# Driver.net
KiCad netlist of a schematic drawn in EAGLE
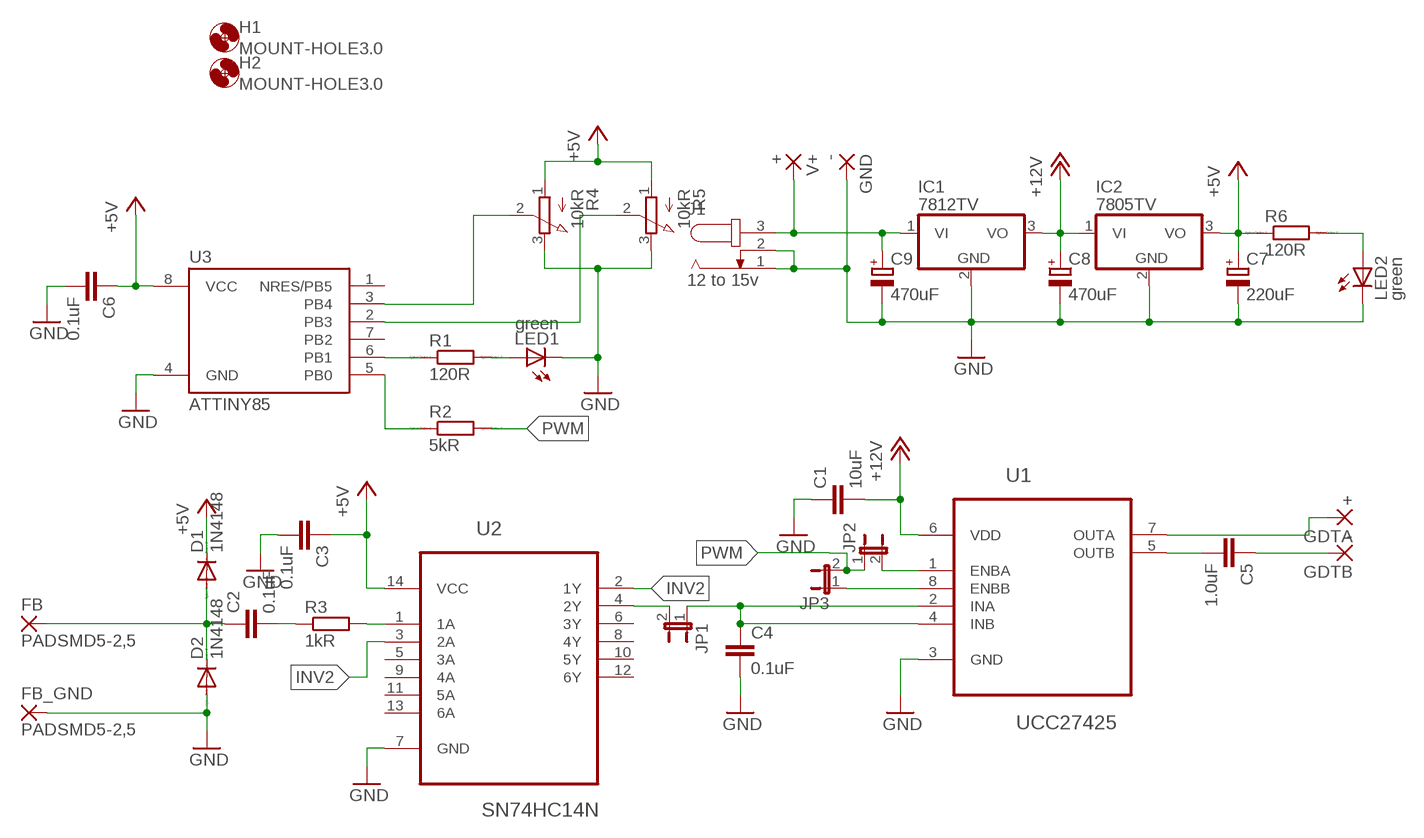
[diagram p0: schematic, sheet 1]

(export (version "E")
  (design (tool "Eeschema 10.0.6"))
  (components
    (comp (ref "C1")
      (value "10uF")
      (footprint "eagle-import:1210")
      (libsource (lib "eagle-import") (part "10UF-1210-50V-20%"))
    )
    (comp (ref "C2")
      (value "0.1uF")
      (footprint "eagle-import:C0805")
      (libsource (lib "eagle-import") (part "C-EUC0805"))
    )
    (comp (ref "C3")
      (value "0.1uF")
      (footprint "eagle-import:C0805")
      (libsource (lib "eagle-import") (part "C-EUC0805"))
    )
    (comp (ref "C4")
      (value "0.1uF")
      (footprint "eagle-import:C0805")
      (libsource (lib "eagle-import") (part "C-EUC0805"))
    )
    (comp (ref "C5")
      (value "1.0uF")
      (footprint "eagle-import:0805")
      (libsource (lib "eagle-import") (part "1.0UF-0805-25V-10%"))
    )
    (comp (ref "C6")
      (value "0.1uF")
      (footprint "eagle-import:C0805")
      (libsource (lib "eagle-import") (part "C-EUC0805"))
    )
    (comp (ref "C7")
      (value "220uF")
      (footprint "eagle-import:E3,5-8")
      (libsource (lib "eagle-import") (part "CPOL-EUE3.5-8"))
    )
    (comp (ref "C8")
      (value "470uF")
      (footprint "eagle-import:E3,5-10")
      (libsource (lib "eagle-import") (part "CPOL-EUE3.5-10"))
    )
    (comp (ref "C9")
      (value "470uF")
      (footprint "eagle-import:E3,5-10")
      (libsource (lib "eagle-import") (part "CPOL-EUE3.5-10"))
    )
    (comp (ref "D1")
      (value "1N4148")
      (footprint "eagle-import:DO35-7")
      (libsource (lib "eagle-import") (part "1N4148DO35-7"))
    )
    (comp (ref "D2")
      (value "1N4148")
      (footprint "eagle-import:DO35-7")
      (libsource (lib "eagle-import") (part "1N4148DO35-7"))
    )
    (comp (ref "FB")
      (value "PADSMD5-2,5")
      (footprint "eagle-import:5-2,5")
      (libsource (lib "eagle-import") (part "WIREPADSMD5-2,5"))
    )
    (comp (ref "FB_GND")
      (value "PADSMD5-2,5")
      (footprint "eagle-import:5-2,5")
      (libsource (lib "eagle-import") (part "WIREPADSMD5-2,5"))
    )
    (comp (ref "GDTA")
      (value "+")
      (footprint "eagle-import:4,16O1,6")
      (libsource (lib "eagle-import") (part "WIREPAD4,16O1,6"))
    )
    (comp (ref "GDTB")
      (value "-")
      (footprint "eagle-import:4,16O1,6")
      (libsource (lib "eagle-import") (part "WIREPAD4,16O1,6"))
    )
    (comp (ref "GND")
      (value "-")
      (footprint "eagle-import:4,16O1,6")
      (libsource (lib "eagle-import") (part "WIREPAD4,16O1,6"))
    )
    (comp (ref "H1")
      (value "MOUNT-HOLE3.0")
      (footprint "eagle-import:3,0")
      (libsource (lib "eagle-import") (part "MOUNT-HOLE3.0"))
    )
    (comp (ref "H2")
      (value "MOUNT-HOLE3.0")
      (footprint "eagle-import:3,0")
      (libsource (lib "eagle-import") (part "MOUNT-HOLE3.0"))
    )
    (comp (ref "IC1")
      (value "7812TV")
      (footprint "eagle-import:TO220V")
      (libsource (lib "eagle-import") (part "78TV12"))
    )
    (comp (ref "IC2")
      (value "7805TV")
      (footprint "eagle-import:TO220V")
      (libsource (lib "eagle-import") (part "78TV05"))
    )
    (comp (ref "J1")
      (value "12 to 15v")
      (footprint "eagle-import:SPC4078")
      (libsource (lib "eagle-import") (part "JACK-PLUG1"))
    )
    (comp (ref "JP1")
      (value "JP1E")
      (footprint "eagle-import:JP1")
      (libsource (lib "eagle-import") (part "JP1E"))
    )
    (comp (ref "JP2")
      (value "JP1E")
      (footprint "eagle-import:JP1")
      (libsource (lib "eagle-import") (part "JP1E"))
    )
    (comp (ref "JP3")
      (value "JP1E")
      (footprint "eagle-import:JP1")
      (libsource (lib "eagle-import") (part "JP1E"))
    )
    (comp (ref "LED1")
      (value "green")
      (footprint "eagle-import:CHIPLED_0805")
      (libsource (lib "eagle-import") (part "LEDCHIPLED_0805"))
    )
    (comp (ref "LED2")
      (value "green")
      (footprint "eagle-import:CHIPLED_0805")
      (libsource (lib "eagle-import") (part "LEDCHIPLED_0805"))
    )
    (comp (ref "R1")
      (value "120R")
      (footprint "eagle-import:R0805")
      (libsource (lib "eagle-import") (part "R"))
    )
    (comp (ref "R2")
      (value "5kR")
      (footprint "eagle-import:R0805")
      (libsource (lib "eagle-import") (part "R"))
    )
    (comp (ref "R3")
      (value "1kR")
      (footprint "eagle-import:R0805")
      (libsource (lib "eagle-import") (part "R-EU_R0805"))
    )
    (comp (ref "R4")
      (value "10kR")
      (footprint "eagle-import:3RP_1610N")
      (libsource (lib "eagle-import") (part "3RP/1610N"))
    )
    (comp (ref "R5")
      (value "10kR")
      (footprint "eagle-import:3RP_1610N")
      (libsource (lib "eagle-import") (part "3RP/1610N"))
    )
    (comp (ref "R6")
      (value "120R")
      (footprint "eagle-import:R0805")
      (libsource (lib "eagle-import") (part "R"))
    )
    (comp (ref "U1")
      (value "UCC27425")
      (footprint "eagle-import:DIP254P762X419-8")
      (libsource (lib "eagle-import") (part "UCC27425QDRQ1DIP_8"))
    )
    (comp (ref "U2")
      (value "SN74HC14N")
      (footprint "eagle-import:DIP254P762X508-14")
      (libsource (lib "eagle-import") (part "SN74HC14N"))
    )
    (comp (ref "U3")
      (value "ATTINY85")
      (footprint "eagle-import:DIL08")
      (libsource (lib "eagle-import") (part "ATTINY85DIL"))
    )
    (comp (ref "V+")
      (value "+")
      (footprint "eagle-import:4,16O1,6")
      (libsource (lib "eagle-import") (part "WIREPAD4,16O1,6"))
    )
  )
  (nets
    (net (code "1") (name "+5V") (class "Default")
      (node (ref "C3") (pin "1") (pinfunction "1_1") (pintype "passive"))
      (node (ref "C6") (pin "1") (pinfunction "1_1") (pintype "passive"))
      (node (ref "C7") (pin "+") (pinfunction "+_+") (pintype "passive"))
      (node (ref "D1") (pin "C") (pinfunction "C_C") (pintype "passive"))
      (node (ref "IC2") (pin "3") (pinfunction "VO_3") (pintype "passive"))
      (node (ref "R4") (pin "1") (pinfunction "A_1") (pintype "passive"))
      (node (ref "R5") (pin "1") (pinfunction "A_1") (pintype "passive"))
      (node (ref "R6") (pin "1") (pinfunction "1_1") (pintype "passive"))
      (node (ref "U2") (pin "14") (pinfunction "VCC_14") (pintype "power_in"))
      (node (ref "U3") (pin "8") (pinfunction "VCC_8") (pintype "power_in"))
    )
    (net (code "2") (name "+12V") (class "Default")
      (node (ref "C1") (pin "2") (pinfunction "2_2") (pintype "passive"))
      (node (ref "C8") (pin "+") (pinfunction "+_+") (pintype "passive"))
      (node (ref "IC1") (pin "3") (pinfunction "VO_3") (pintype "passive"))
      (node (ref "IC2") (pin "1") (pinfunction "VI_1") (pintype "input"))
      (node (ref "U1") (pin "6") (pinfunction "VDD_6") (pintype "power_in"))
    )
    (net (code "3") (name "GND") (class "Default")
      (node (ref "C1") (pin "1") (pinfunction "1_1") (pintype "passive"))
      (node (ref "C3") (pin "2") (pinfunction "2_2") (pintype "passive"))
      (node (ref "C4") (pin "2") (pinfunction "2_2") (pintype "passive"))
      (node (ref "C6") (pin "2") (pinfunction "2_2") (pintype "passive"))
      (node (ref "C7") (pin "-") (pinfunction "-_-") (pintype "passive"))
      (node (ref "C8") (pin "-") (pinfunction "-_-") (pintype "passive"))
      (node (ref "C9") (pin "-") (pinfunction "-_-") (pintype "passive"))
      (node (ref "D2") (pin "A") (pinfunction "A_A") (pintype "passive"))
      (node (ref "FB_GND") (pin "1") (pinfunction "P_1") (pintype "passive"))
      (node (ref "GND") (pin "1") (pinfunction "P_1") (pintype "passive"))
      (node (ref "IC1") (pin "2") (pinfunction "GND_2") (pintype "passive"))
      (node (ref "IC2") (pin "2") (pinfunction "GND_2") (pintype "passive"))
      (node (ref "J1") (pin "1") (pinfunction "1_1") (pintype "passive"))
      (node (ref "J1") (pin "2") (pinfunction "2_2") (pintype "passive"))
      (node (ref "LED1") (pin "C") (pinfunction "C_C") (pintype "passive"))
      (node (ref "LED2") (pin "C") (pinfunction "C_C") (pintype "passive"))
      (node (ref "R4") (pin "3") (pinfunction "E_3") (pintype "passive"))
      (node (ref "R5") (pin "3") (pinfunction "E_3") (pintype "passive"))
      (node (ref "U1") (pin "3") (pinfunction "GND_3") (pintype "passive"))
      (node (ref "U2") (pin "7") (pinfunction "GND_7") (pintype "passive"))
      (node (ref "U3") (pin "4") (pinfunction "GND_4") (pintype "power_in"))
    )
    (net (code "4") (name "INV2") (class "Default")
      (node (ref "U2") (pin "2") (pinfunction "1Y_2") (pintype "output"))
      (node (ref "U2") (pin "3") (pinfunction "2A_3") (pintype "input"))
    )
    (net (code "5") (name "Net-(C2-Pad2)") (class "Default")
      (node (ref "C2") (pin "2") (pinfunction "2_2") (pintype "passive"))
      (node (ref "R3") (pin "1") (pinfunction "1_1") (pintype "passive"))
    )
    (net (code "6") (name "Net-(FB-P)") (class "Default")
      (node (ref "C2") (pin "1") (pinfunction "1_1") (pintype "passive"))
      (node (ref "D1") (pin "A") (pinfunction "A_A") (pintype "passive"))
      (node (ref "D2") (pin "C") (pinfunction "C_C") (pintype "passive"))
      (node (ref "FB") (pin "1") (pinfunction "P_1") (pintype "passive"))
    )
    (net (code "7") (name "Net-(GDTA-P)") (class "Default")
      (node (ref "GDTA") (pin "1") (pinfunction "P_1") (pintype "passive"))
      (node (ref "U1") (pin "7") (pinfunction "OUTA_7") (pintype "output"))
    )
    (net (code "8") (name "Net-(GDTB-P)") (class "Default")
      (node (ref "C5") (pin "1") (pinfunction "1_1") (pintype "passive"))
      (node (ref "GDTB") (pin "1") (pinfunction "P_1") (pintype "passive"))
    )
    (net (code "9") (name "Net-(IC1-VI)") (class "Default")
      (node (ref "C9") (pin "+") (pinfunction "+_+") (pintype "passive"))
      (node (ref "IC1") (pin "1") (pinfunction "VI_1") (pintype "input"))
      (node (ref "J1") (pin "3") (pinfunction "3_3") (pintype "passive"))
      (node (ref "V+") (pin "1") (pinfunction "P_1") (pintype "passive"))
    )
    (net (code "10") (name "Net-(LED1-PadA)") (class "Default")
      (node (ref "LED1") (pin "A") (pinfunction "A_A") (pintype "passive"))
      (node (ref "R1") (pin "2") (pinfunction "2_2") (pintype "passive"))
    )
    (net (code "11") (name "Net-(LED2-PadA)") (class "Default")
      (node (ref "LED2") (pin "A") (pinfunction "A_A") (pintype "passive"))
      (node (ref "R6") (pin "2") (pinfunction "2_2") (pintype "passive"))
    )
    (net (code "12") (name "Net-(R4-S)") (class "Default")
      (node (ref "R4") (pin "2") (pinfunction "S_2") (pintype "passive"))
      (node (ref "U3") (pin "3") (pinfunction "PB4_3") (pintype "bidirectional"))
    )
    (net (code "13") (name "Net-(R5-S)") (class "Default")
      (node (ref "R5") (pin "2") (pinfunction "S_2") (pintype "passive"))
      (node (ref "U3") (pin "2") (pinfunction "PB3_2") (pintype "bidirectional"))
    )
    (net (code "14") (name "Net-(U1-ENBA)") (class "Default")
      (node (ref "JP2") (pin "2") (pinfunction "2_2") (pintype "passive"))
      (node (ref "U1") (pin "1") (pinfunction "ENBA_1") (pintype "input"))
    )
    (net (code "15") (name "Net-(U1-ENBB)") (class "Default")
      (node (ref "JP3") (pin "1") (pinfunction "1_1") (pintype "passive"))
      (node (ref "U1") (pin "8") (pinfunction "ENBB_8") (pintype "input"))
    )
    (net (code "16") (name "Net-(U1-INA)") (class "Default")
      (node (ref "C4") (pin "1") (pinfunction "1_1") (pintype "passive"))
      (node (ref "JP1") (pin "1") (pinfunction "1_1") (pintype "passive"))
      (node (ref "U1") (pin "2") (pinfunction "INA_2") (pintype "input"))
      (node (ref "U1") (pin "4") (pinfunction "INB_4") (pintype "input"))
    )
    (net (code "17") (name "Net-(U1-OUTB)") (class "Default")
      (node (ref "C5") (pin "2") (pinfunction "2_2") (pintype "passive"))
      (node (ref "U1") (pin "5") (pinfunction "OUTB_5") (pintype "output"))
    )
    (net (code "18") (name "Net-(U2-1A)") (class "Default")
      (node (ref "R3") (pin "2") (pinfunction "2_2") (pintype "passive"))
      (node (ref "U2") (pin "1") (pinfunction "1A_1") (pintype "input"))
    )
    (net (code "19") (name "Net-(U2-2Y)") (class "Default")
      (node (ref "JP1") (pin "2") (pinfunction "2_2") (pintype "passive"))
      (node (ref "U2") (pin "4") (pinfunction "2Y_4") (pintype "output"))
    )
    (net (code "20") (name "Net-(U3-PB0)") (class "Default")
      (node (ref "R2") (pin "1") (pinfunction "1_1") (pintype "passive"))
      (node (ref "U3") (pin "5") (pinfunction "PB0_5") (pintype "bidirectional"))
    )
    (net (code "21") (name "Net-(U3-PB1)") (class "Default")
      (node (ref "R1") (pin "1") (pinfunction "1_1") (pintype "passive"))
      (node (ref "U3") (pin "6") (pinfunction "PB1_6") (pintype "bidirectional"))
    )
    (net (code "22") (name "PWM") (class "Default")
      (node (ref "JP2") (pin "1") (pinfunction "1_1") (pintype "passive"))
      (node (ref "JP3") (pin "2") (pinfunction "2_2") (pintype "passive"))
      (node (ref "R2") (pin "2") (pinfunction "2_2") (pintype "passive"))
    )
    (net (code "23") (name "unconnected-(U2-3A-Pad5)") (class "Default")
      (node (ref "U2") (pin "5") (pinfunction "3A_5") (pintype "input"))
    )
    (net (code "24") (name "unconnected-(U2-3Y-Pad6)") (class "Default")
      (node (ref "U2") (pin "6") (pinfunction "3Y_6") (pintype "output"))
    )
    (net (code "25") (name "unconnected-(U2-4A-Pad9)") (class "Default")
      (node (ref "U2") (pin "9") (pinfunction "4A_9") (pintype "input"))
    )
    (net (code "26") (name "unconnected-(U2-4Y-Pad8)") (class "Default")
      (node (ref "U2") (pin "8") (pinfunction "4Y_8") (pintype "output"))
    )
    (net (code "27") (name "unconnected-(U2-5A-Pad11)") (class "Default")
      (node (ref "U2") (pin "11") (pinfunction "5A_11") (pintype "input"))
    )
    (net (code "28") (name "unconnected-(U2-5Y-Pad10)") (class "Default")
      (node (ref "U2") (pin "10") (pinfunction "5Y_10") (pintype "output"))
    )
    (net (code "29") (name "unconnected-(U2-6A-Pad13)") (class "Default")
      (node (ref "U2") (pin "13") (pinfunction "6A_13") (pintype "input"))
    )
    (net (code "30") (name "unconnected-(U2-6Y-Pad12)") (class "Default")
      (node (ref "U2") (pin "12") (pinfunction "6Y_12") (pintype "output"))
    )
    (net (code "31") (name "unconnected-(U3-NRES{slash}PB5-Pad1)") (class "Default")
      (node (ref "U3") (pin "1") (pinfunction "NRES/PB5_1") (pintype "bidirectional"))
    )
    (net (code "32") (name "unconnected-(U3-PB2-Pad7)") (class "Default")
      (node (ref "U3") (pin "7") (pinfunction "PB2_7") (pintype "bidirectional"))
    )
  )
)
